# wemos-boost-rev-1b.net
KiCad netlist of a schematic drawn in EAGLE
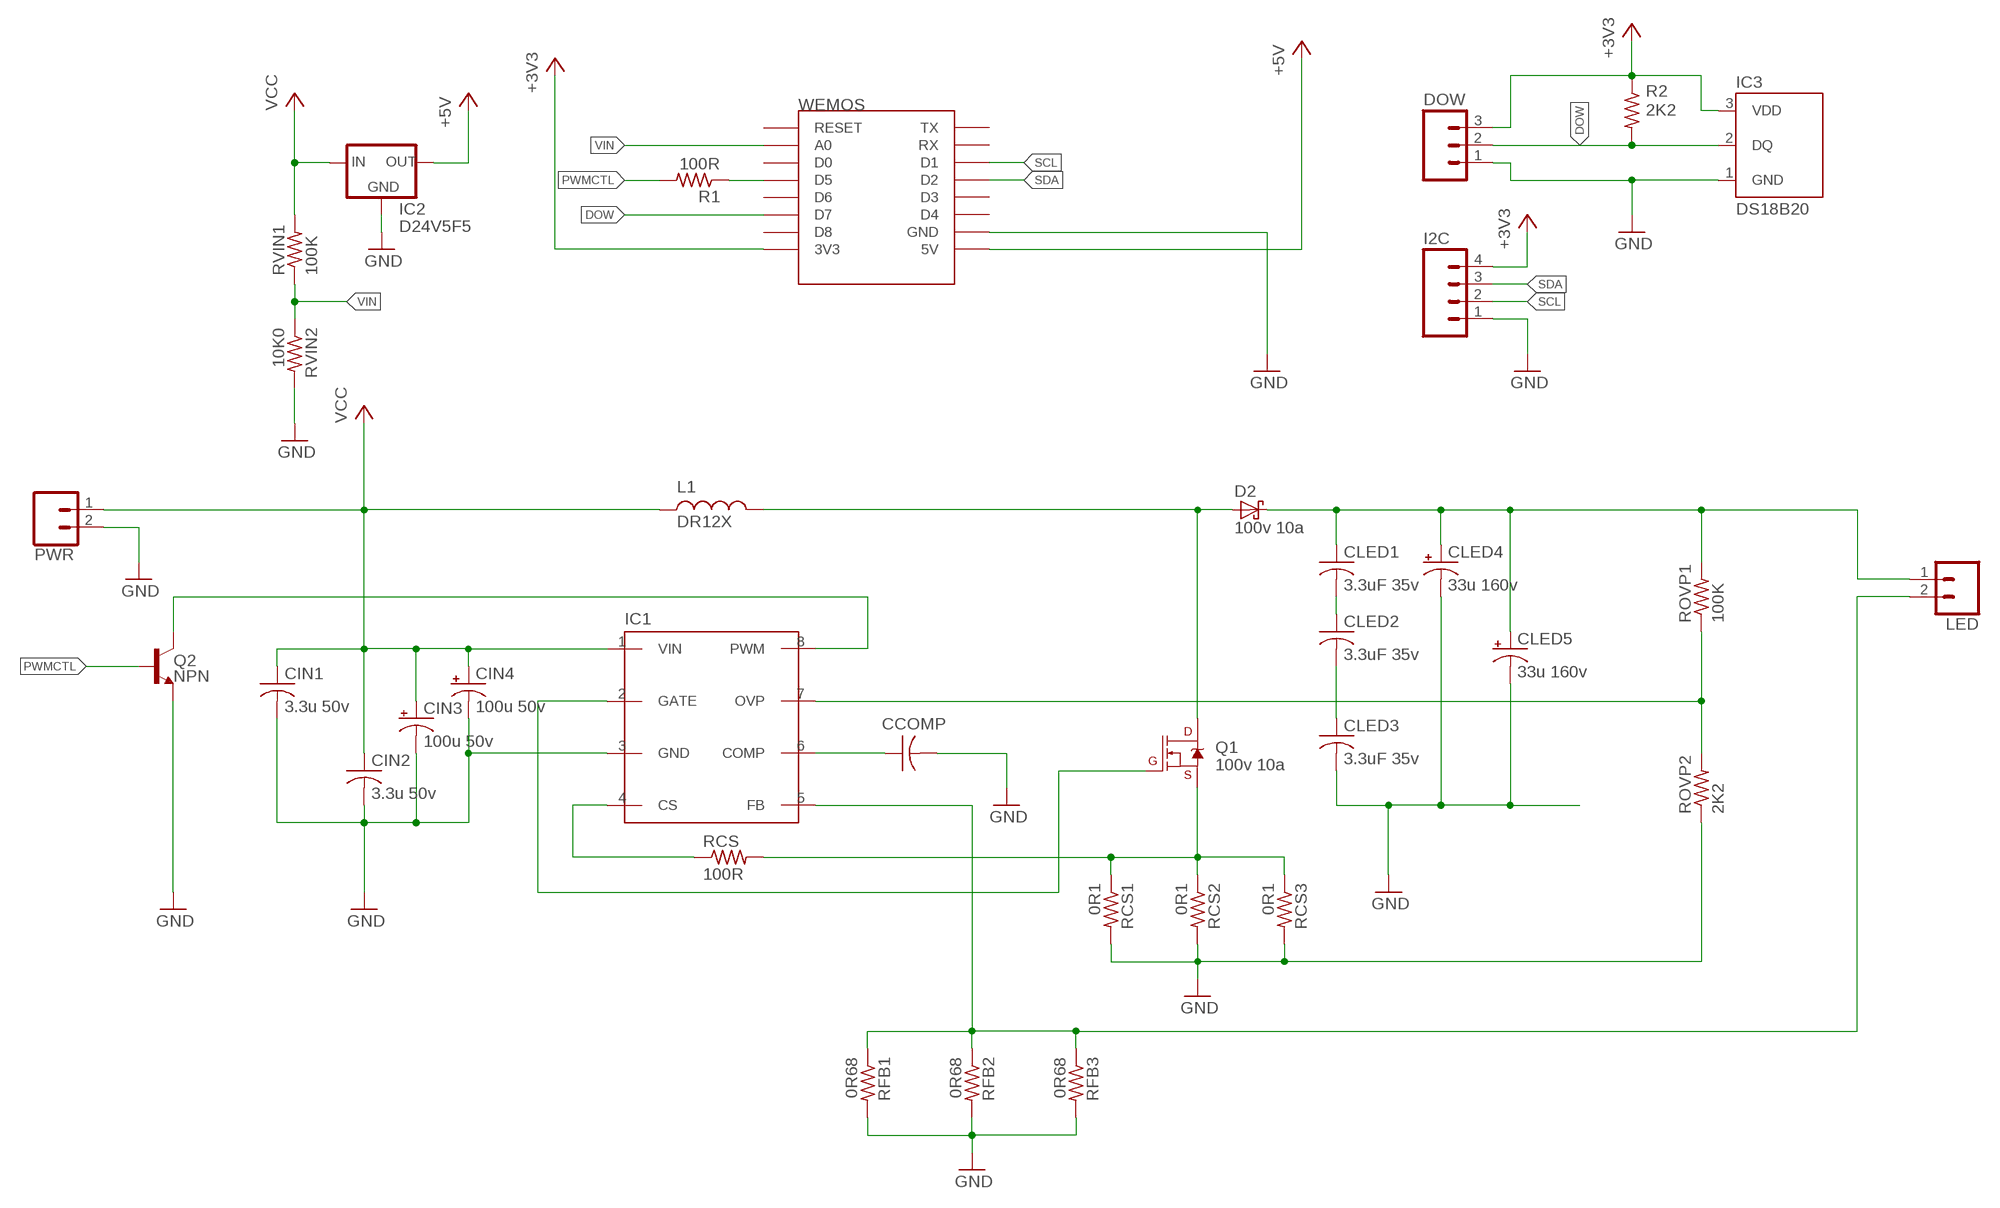
[diagram p0: schematic, sheet 1]

(export (version "E")
  (design (tool "Eeschema 10.0.6"))
  (components
    (comp (ref "CCOMP")
      (value "C-USC0603")
      (footprint "eagle-import:C0603")
      (libsource (lib "eagle-import") (part "C-USC0603"))
    )
    (comp (ref "CIN1")
      (value "3.3u 50v")
      (footprint "eagle-import:C1210")
      (libsource (lib "eagle-import") (part "C-USC1210"))
    )
    (comp (ref "CIN2")
      (value "3.3u 50v")
      (footprint "eagle-import:C1210")
      (libsource (lib "eagle-import") (part "C-USC1210"))
    )
    (comp (ref "CIN3")
      (value "100u 50v")
      (footprint "eagle-import:PANASONIC_F")
      (libsource (lib "eagle-import") (part "CPOL-USF"))
    )
    (comp (ref "CIN4")
      (value "100u 50v")
      (footprint "eagle-import:PANASONIC_F")
      (libsource (lib "eagle-import") (part "CPOL-USF"))
    )
    (comp (ref "CLED1")
      (value "3.3uF 35v")
      (footprint "eagle-import:C0805")
      (libsource (lib "eagle-import") (part "C-USC0805"))
    )
    (comp (ref "CLED2")
      (value "3.3uF 35v")
      (footprint "eagle-import:C0805")
      (libsource (lib "eagle-import") (part "C-USC0805"))
    )
    (comp (ref "CLED3")
      (value "3.3uF 35v")
      (footprint "eagle-import:C0805")
      (libsource (lib "eagle-import") (part "C-USC0805"))
    )
    (comp (ref "CLED4")
      (value "33u 160v")
      (footprint "eagle-import:PANASONIC_G")
      (libsource (lib "eagle-import") (part "CPOL-USG"))
    )
    (comp (ref "CLED5")
      (value "33u 160v")
      (footprint "eagle-import:PANASONIC_G")
      (libsource (lib "eagle-import") (part "CPOL-USG"))
    )
    (comp (ref "D2")
      (value "100v 10a")
      (footprint "eagle-import:SMB")
      (libsource (lib "eagle-import") (part "SCHOTTKY-SMB"))
    )
    (comp (ref "DOW")
      (value "M03SCREW_LOCK")
      (footprint "eagle-import:SCREWTERMINAL-3.5MM-3_LOCK.007S")
      (libsource (lib "eagle-import") (part "M03SCREW_LOCK"))
    )
    (comp (ref "I2C")
      (value "M04SCREW_LOCK")
      (footprint "eagle-import:SCREWTERMINAL-3.5MM-4_LOCK")
      (libsource (lib "eagle-import") (part "M04SCREW_LOCK"))
    )
    (comp (ref "IC1")
      (value "AL8853S-13")
      (footprint "eagle-import:SOP08")
      (libsource (lib "eagle-import") (part "AL8853S-13"))
    )
    (comp (ref "IC2")
      (value "D24V5F5")
      (footprint "eagle-import:78XXS")
      (libsource (lib "eagle-import") (part "78XXS"))
    )
    (comp (ref "IC3")
      (value "DS18B20")
      (footprint "eagle-import:TO-92-AMMO")
      (libsource (lib "eagle-import") (part "DS18B20"))
    )
    (comp (ref "L1")
      (value "DR12X")
      (footprint "eagle-import:DR12X")
      (libsource (lib "eagle-import") (part "DR12X"))
    )
    (comp (ref "LED")
      (value "CONN_025MM")
      (footprint "eagle-import:SCREWTERMINAL-5MM-2")
      (libsource (lib "eagle-import") (part "CONN_025MM"))
    )
    (comp (ref "PWR")
      (value "CONN_025MM")
      (footprint "eagle-import:SCREWTERMINAL-5MM-2")
      (libsource (lib "eagle-import") (part "CONN_025MM"))
    )
    (comp (ref "Q1")
      (value "100v 10a")
      (footprint "eagle-import:TO-252_DPAK")
      (libsource (lib "eagle-import") (part "MOSFET-NCH-FDD8780"))
    )
    (comp (ref "Q2")
      (value "NPN")
      (footprint "eagle-import:SOT23-3")
      (libsource (lib "eagle-import") (part "TRANS_NPN-MMBT2222AL"))
    )
    (comp (ref "R1")
      (value "100R")
      (footprint "eagle-import:R0603")
      (libsource (lib "eagle-import") (part "R-US_R0603"))
    )
    (comp (ref "R2")
      (value "2K2")
      (footprint "eagle-import:R0603")
      (libsource (lib "eagle-import") (part "R-US_R0603"))
    )
    (comp (ref "RCS")
      (value "100R")
      (footprint "eagle-import:R0603")
      (libsource (lib "eagle-import") (part "R-US_R0603"))
    )
    (comp (ref "RCS1")
      (value "0R1")
      (footprint "eagle-import:R2010")
      (libsource (lib "eagle-import") (part "R-US_R2010"))
    )
    (comp (ref "RCS2")
      (value "0R1")
      (footprint "eagle-import:R2010")
      (libsource (lib "eagle-import") (part "R-US_R2010"))
    )
    (comp (ref "RCS3")
      (value "0R1")
      (footprint "eagle-import:R2010")
      (libsource (lib "eagle-import") (part "R-US_R2010"))
    )
    (comp (ref "RFB1")
      (value "0R68")
      (footprint "eagle-import:R1206")
      (libsource (lib "eagle-import") (part "R-US_R1206"))
    )
    (comp (ref "RFB2")
      (value "0R68")
      (footprint "eagle-import:R1206")
      (libsource (lib "eagle-import") (part "R-US_R1206"))
    )
    (comp (ref "RFB3")
      (value "0R68")
      (footprint "eagle-import:R1206")
      (libsource (lib "eagle-import") (part "R-US_R1206"))
    )
    (comp (ref "ROVP1")
      (value "100K")
      (footprint "eagle-import:R0603")
      (libsource (lib "eagle-import") (part "R-US_R0603"))
    )
    (comp (ref "ROVP2")
      (value "2K2")
      (footprint "eagle-import:R0603")
      (libsource (lib "eagle-import") (part "R-US_R0603"))
    )
    (comp (ref "RVIN1")
      (value "100K")
      (footprint "eagle-import:R0603")
      (libsource (lib "eagle-import") (part "R-US_R0603"))
    )
    (comp (ref "RVIN2")
      (value "10K0")
      (footprint "eagle-import:R0603")
      (libsource (lib "eagle-import") (part "R-US_R0603"))
    )
    (comp (ref "WEMOS")
      (value "WEMOS-D1-MINI")
      (footprint "eagle-import:WEMOS-D1-MINI")
      (libsource (lib "eagle-import") (part "WEMOS-D1-MINI"))
    )
  )
  (nets
    (net (code "1") (name "+3V3") (class "Default")
      (node (ref "DOW") (pin "3") (pinfunction "3_3") (pintype "passive"))
      (node (ref "I2C") (pin "4") (pinfunction "4_4") (pintype "passive"))
      (node (ref "IC3") (pin "3") (pinfunction "VDD_3") (pintype "power_in"))
      (node (ref "R2") (pin "1") (pinfunction "1_1") (pintype "passive"))
      (node (ref "WEMOS") (pin "3V3") (pinfunction "3V3_3V3") (pintype "bidirectional"))
    )
    (net (code "2") (name "+5V") (class "Default")
      (node (ref "IC2") (pin "OUT") (pinfunction "OUT_OUT") (pintype "passive"))
      (node (ref "WEMOS") (pin "5V") (pinfunction "5V_5V") (pintype "bidirectional"))
    )
    (net (code "3") (name "DOW") (class "Default")
      (node (ref "DOW") (pin "2") (pinfunction "2_2") (pintype "passive"))
      (node (ref "IC3") (pin "2") (pinfunction "DQ_2") (pintype "bidirectional"))
      (node (ref "R2") (pin "2") (pinfunction "2_2") (pintype "passive"))
      (node (ref "WEMOS") (pin "D7") (pinfunction "D7_D7") (pintype "bidirectional"))
    )
    (net (code "4") (name "GND") (class "Default")
      (node (ref "CCOMP") (pin "2") (pinfunction "2_2") (pintype "passive"))
      (node (ref "CIN1") (pin "2") (pinfunction "2_2") (pintype "passive"))
      (node (ref "CIN2") (pin "2") (pinfunction "2_2") (pintype "passive"))
      (node (ref "CIN3") (pin "-") (pinfunction "-_-") (pintype "passive"))
      (node (ref "CIN4") (pin "-") (pinfunction "-_-") (pintype "passive"))
      (node (ref "CLED3") (pin "2") (pinfunction "2_2") (pintype "passive"))
      (node (ref "CLED4") (pin "-") (pinfunction "-_-") (pintype "passive"))
      (node (ref "CLED5") (pin "-") (pinfunction "-_-") (pintype "passive"))
      (node (ref "DOW") (pin "1") (pinfunction "1_1") (pintype "passive"))
      (node (ref "I2C") (pin "1") (pinfunction "1_1") (pintype "passive"))
      (node (ref "IC1") (pin "3") (pinfunction "GND_3") (pintype "power_in"))
      (node (ref "IC2") (pin "GND") (pinfunction "GND_GND") (pintype "input"))
      (node (ref "IC3") (pin "1") (pinfunction "GND_1") (pintype "power_in"))
      (node (ref "PWR") (pin "2") (pinfunction "2_2") (pintype "passive"))
      (node (ref "Q2") (pin "2") (pinfunction "E_2") (pintype "passive"))
      (node (ref "RCS1") (pin "2") (pinfunction "2_2") (pintype "passive"))
      (node (ref "RCS2") (pin "2") (pinfunction "2_2") (pintype "passive"))
      (node (ref "RCS3") (pin "2") (pinfunction "2_2") (pintype "passive"))
      (node (ref "RFB1") (pin "2") (pinfunction "2_2") (pintype "passive"))
      (node (ref "RFB2") (pin "2") (pinfunction "2_2") (pintype "passive"))
      (node (ref "RFB3") (pin "2") (pinfunction "2_2") (pintype "passive"))
      (node (ref "ROVP2") (pin "1") (pinfunction "1_1") (pintype "passive"))
      (node (ref "RVIN2") (pin "2") (pinfunction "2_2") (pintype "passive"))
      (node (ref "WEMOS") (pin "GND") (pinfunction "GND_GND") (pintype "bidirectional"))
    )
    (net (code "5") (name "Net-(CLED1-Pad1)") (class "Default")
      (node (ref "CLED1") (pin "1") (pinfunction "1_1") (pintype "passive"))
      (node (ref "CLED4") (pin "+") (pinfunction "+_+") (pintype "passive"))
      (node (ref "CLED5") (pin "+") (pinfunction "+_+") (pintype "passive"))
      (node (ref "D2") (pin "K") (pinfunction "K_K") (pintype "passive"))
      (node (ref "LED") (pin "1") (pinfunction "1_1") (pintype "passive"))
      (node (ref "ROVP1") (pin "2") (pinfunction "2_2") (pintype "passive"))
    )
    (net (code "6") (name "Net-(CLED1-Pad2)") (class "Default")
      (node (ref "CLED1") (pin "2") (pinfunction "2_2") (pintype "passive"))
      (node (ref "CLED2") (pin "1") (pinfunction "1_1") (pintype "passive"))
    )
    (net (code "7") (name "Net-(CLED2-Pad2)") (class "Default")
      (node (ref "CLED2") (pin "2") (pinfunction "2_2") (pintype "passive"))
      (node (ref "CLED3") (pin "1") (pinfunction "1_1") (pintype "passive"))
    )
    (net (code "8") (name "Net-(IC1-COMP)") (class "Default")
      (node (ref "CCOMP") (pin "1") (pinfunction "1_1") (pintype "passive"))
      (node (ref "IC1") (pin "6") (pinfunction "COMP_6") (pintype "input"))
    )
    (net (code "9") (name "Net-(IC1-CS)") (class "Default")
      (node (ref "IC1") (pin "4") (pinfunction "CS_4") (pintype "input"))
      (node (ref "RCS") (pin "1") (pinfunction "1_1") (pintype "passive"))
    )
    (net (code "10") (name "Net-(IC1-FB)") (class "Default")
      (node (ref "IC1") (pin "5") (pinfunction "FB_5") (pintype "input"))
      (node (ref "LED") (pin "2") (pinfunction "2_2") (pintype "passive"))
      (node (ref "RFB1") (pin "1") (pinfunction "1_1") (pintype "passive"))
      (node (ref "RFB2") (pin "1") (pinfunction "1_1") (pintype "passive"))
      (node (ref "RFB3") (pin "1") (pinfunction "1_1") (pintype "passive"))
    )
    (net (code "11") (name "Net-(IC1-GATE)") (class "Default")
      (node (ref "IC1") (pin "2") (pinfunction "GATE_2") (pintype "output"))
      (node (ref "Q1") (pin "1") (pinfunction "G_1") (pintype "bidirectional"))
    )
    (net (code "12") (name "Net-(IC1-OVP)") (class "Default")
      (node (ref "IC1") (pin "7") (pinfunction "OVP_7") (pintype "input"))
      (node (ref "ROVP1") (pin "1") (pinfunction "1_1") (pintype "passive"))
      (node (ref "ROVP2") (pin "2") (pinfunction "2_2") (pintype "passive"))
    )
    (net (code "13") (name "Net-(IC1-PWM)") (class "Default")
      (node (ref "IC1") (pin "8") (pinfunction "PWM_8") (pintype "input"))
      (node (ref "Q2") (pin "3") (pinfunction "C_3") (pintype "passive"))
    )
    (net (code "14") (name "Net-(Q1-D)") (class "Default")
      (node (ref "D2") (pin "A") (pinfunction "A_A") (pintype "passive"))
      (node (ref "L1") (pin "P$1") (pinfunction "P$1_P$1") (pintype "passive"))
      (node (ref "Q1") (pin "2") (pinfunction "D_2") (pintype "bidirectional"))
    )
    (net (code "15") (name "Net-(Q1-S)") (class "Default")
      (node (ref "Q1") (pin "3") (pinfunction "S_3") (pintype "bidirectional"))
      (node (ref "RCS") (pin "2") (pinfunction "2_2") (pintype "passive"))
      (node (ref "RCS1") (pin "1") (pinfunction "1_1") (pintype "passive"))
      (node (ref "RCS2") (pin "1") (pinfunction "1_1") (pintype "passive"))
      (node (ref "RCS3") (pin "1") (pinfunction "1_1") (pintype "passive"))
    )
    (net (code "16") (name "Net-(R1-Pad1)") (class "Default")
      (node (ref "R1") (pin "1") (pinfunction "1_1") (pintype "passive"))
      (node (ref "WEMOS") (pin "D5") (pinfunction "D5_D5") (pintype "bidirectional"))
    )
    (net (code "17") (name "PWMCTL") (class "Default")
      (node (ref "Q2") (pin "1") (pinfunction "B_1") (pintype "passive"))
      (node (ref "R1") (pin "2") (pinfunction "2_2") (pintype "passive"))
    )
    (net (code "18") (name "SCL") (class "Default")
      (node (ref "I2C") (pin "2") (pinfunction "2_2") (pintype "passive"))
      (node (ref "WEMOS") (pin "D1") (pinfunction "D1_D1") (pintype "bidirectional"))
    )
    (net (code "19") (name "SDA") (class "Default")
      (node (ref "I2C") (pin "3") (pinfunction "3_3") (pintype "passive"))
      (node (ref "WEMOS") (pin "D2") (pinfunction "D2_D2") (pintype "bidirectional"))
    )
    (net (code "20") (name "VCC") (class "Default")
      (node (ref "CIN1") (pin "1") (pinfunction "1_1") (pintype "passive"))
      (node (ref "CIN2") (pin "1") (pinfunction "1_1") (pintype "passive"))
      (node (ref "CIN3") (pin "+") (pinfunction "+_+") (pintype "passive"))
      (node (ref "CIN4") (pin "+") (pinfunction "+_+") (pintype "passive"))
      (node (ref "IC1") (pin "1") (pinfunction "VIN_1") (pintype "power_in"))
      (node (ref "IC2") (pin "IN") (pinfunction "IN_IN") (pintype "input"))
      (node (ref "L1") (pin "P$2") (pinfunction "P$2_P$2") (pintype "passive"))
      (node (ref "PWR") (pin "1") (pinfunction "1_1") (pintype "passive"))
      (node (ref "RVIN1") (pin "2") (pinfunction "2_2") (pintype "passive"))
    )
    (net (code "21") (name "VIN") (class "Default")
      (node (ref "RVIN1") (pin "1") (pinfunction "1_1") (pintype "passive"))
      (node (ref "RVIN2") (pin "1") (pinfunction "1_1") (pintype "passive"))
      (node (ref "WEMOS") (pin "A0") (pinfunction "A0_A0") (pintype "bidirectional"))
    )
    (net (code "22") (name "unconnected-(WEMOS-PadD0)") (class "Default")
      (node (ref "WEMOS") (pin "D0") (pinfunction "D0_D0") (pintype "bidirectional"))
    )
    (net (code "23") (name "unconnected-(WEMOS-PadD3)") (class "Default")
      (node (ref "WEMOS") (pin "D3") (pinfunction "D3_D3") (pintype "bidirectional"))
    )
    (net (code "24") (name "unconnected-(WEMOS-PadD4)") (class "Default")
      (node (ref "WEMOS") (pin "D4") (pinfunction "D4_D4") (pintype "bidirectional"))
    )
    (net (code "25") (name "unconnected-(WEMOS-PadD6)") (class "Default")
      (node (ref "WEMOS") (pin "D6") (pinfunction "D6_D6") (pintype "bidirectional"))
    )
    (net (code "26") (name "unconnected-(WEMOS-PadD8)") (class "Default")
      (node (ref "WEMOS") (pin "D8") (pinfunction "D8_D8") (pintype "bidirectional"))
    )
    (net (code "27") (name "unconnected-(WEMOS-PadRESET)") (class "Default")
      (node (ref "WEMOS") (pin "RESET") (pinfunction "RESET_RESET") (pintype "bidirectional"))
    )
    (net (code "28") (name "unconnected-(WEMOS-PadRX)") (class "Default")
      (node (ref "WEMOS") (pin "RX") (pinfunction "RX_RX") (pintype "bidirectional"))
    )
    (net (code "29") (name "unconnected-(WEMOS-PadTX)") (class "Default")
      (node (ref "WEMOS") (pin "TX") (pinfunction "TX_TX") (pintype "bidirectional"))
    )
  )
)
